# Processor_Interface.net
KiCad netlist of a schematic drawn in Altium Designer
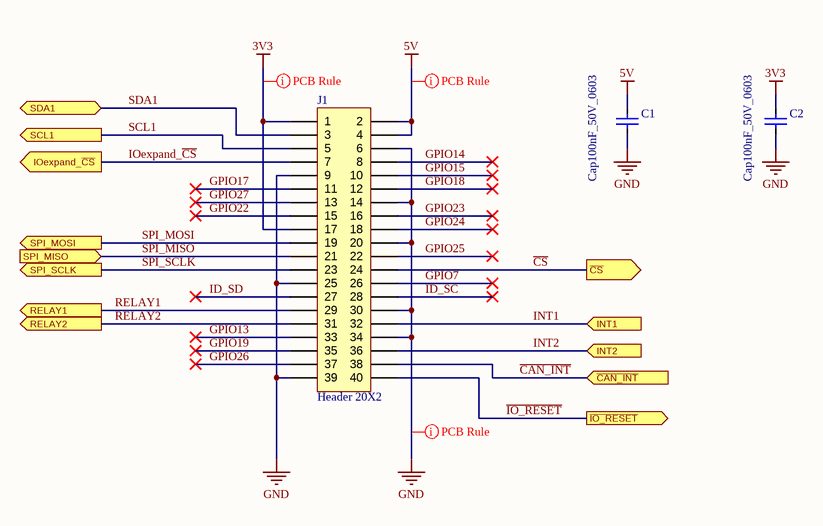
[diagram p0: Processor_Interface.SchDoc]

(export (version "E")
  (design (tool "Eeschema 10.0.6"))
  (components
    (comp (ref "C1")
      (value "Cap100nF_50V_0603")
      (footprint "0603C_L")
      (libsource (lib " Advanced] Training Course - A365") (part "CAP General"))
    )
    (comp (ref "C2")
      (value "Cap100nF_50V_0603")
      (footprint "0603C_L")
      (libsource (lib " Advanced] Training Course - A365") (part "CAP General"))
    )
    (comp (ref "J1")
      (value "Header 20X2")
      (footprint "HDR2X20")
      (description "Header, 20-Pin, Dual row")
      (fields (field (name "PUBLISHER") "Altium Limited"))
      (libsource (lib " Advanced] Training Course - A365") (part "Header 20X2"))
    )
  )
  (nets
    (net (code "1") (name "/CAN_INT") (class "Default")
      (node (ref "J1") (pin "38") (pinfunction "38_38") (pintype "passive"))
    )
    (net (code "2") (name "/GPIO7") (class "Default")
      (node (ref "J1") (pin "26") (pinfunction "26_26") (pintype "passive+no_connect"))
    )
    (net (code "3") (name "/GPIO13") (class "Default")
      (node (ref "J1") (pin "33") (pinfunction "33_33") (pintype "passive+no_connect"))
    )
    (net (code "4") (name "/GPIO14") (class "Default")
      (node (ref "J1") (pin "8") (pinfunction "8_8") (pintype "passive+no_connect"))
    )
    (net (code "5") (name "/GPIO15") (class "Default")
      (node (ref "J1") (pin "10") (pinfunction "10_10") (pintype "passive+no_connect"))
    )
    (net (code "6") (name "/GPIO17") (class "Default")
      (node (ref "J1") (pin "11") (pinfunction "11_11") (pintype "passive+no_connect"))
    )
    (net (code "7") (name "/GPIO18") (class "Default")
      (node (ref "J1") (pin "12") (pinfunction "12_12") (pintype "passive+no_connect"))
    )
    (net (code "8") (name "/GPIO19") (class "Default")
      (node (ref "J1") (pin "35") (pinfunction "35_35") (pintype "passive+no_connect"))
    )
    (net (code "9") (name "/GPIO22") (class "Default")
      (node (ref "J1") (pin "15") (pinfunction "15_15") (pintype "passive+no_connect"))
    )
    (net (code "10") (name "/GPIO23") (class "Default")
      (node (ref "J1") (pin "16") (pinfunction "16_16") (pintype "passive+no_connect"))
    )
    (net (code "11") (name "/GPIO24") (class "Default")
      (node (ref "J1") (pin "18") (pinfunction "18_18") (pintype "passive+no_connect"))
    )
    (net (code "12") (name "/GPIO25") (class "Default")
      (node (ref "J1") (pin "22") (pinfunction "22_22") (pintype "passive+no_connect"))
    )
    (net (code "13") (name "/GPIO26") (class "Default")
      (node (ref "J1") (pin "37") (pinfunction "37_37") (pintype "passive+no_connect"))
    )
    (net (code "14") (name "/GPIO27") (class "Default")
      (node (ref "J1") (pin "13") (pinfunction "13_13") (pintype "passive+no_connect"))
    )
    (net (code "15") (name "/ID_SC") (class "Default")
      (node (ref "J1") (pin "28") (pinfunction "28_28") (pintype "passive+no_connect"))
    )
    (net (code "16") (name "/ID_SD") (class "Default")
      (node (ref "J1") (pin "27") (pinfunction "27_27") (pintype "passive+no_connect"))
    )
    (net (code "17") (name "/INT1") (class "Default")
      (node (ref "J1") (pin "32") (pinfunction "32_32") (pintype "passive"))
    )
    (net (code "18") (name "/INT2") (class "Default")
      (node (ref "J1") (pin "36") (pinfunction "36_36") (pintype "passive"))
    )
    (net (code "19") (name "/IO_RESET") (class "Default")
      (node (ref "J1") (pin "40") (pinfunction "40_40") (pintype "passive"))
    )
    (net (code "20") (name "/IOexpand_~{CS}") (class "Default")
      (node (ref "J1") (pin "7") (pinfunction "7_7") (pintype "passive"))
    )
    (net (code "21") (name "/RELAY1") (class "Default")
      (node (ref "J1") (pin "29") (pinfunction "29_29") (pintype "passive"))
    )
    (net (code "22") (name "/RELAY2") (class "Default")
      (node (ref "J1") (pin "31") (pinfunction "31_31") (pintype "passive"))
    )
    (net (code "23") (name "/SCL1") (class "Default")
      (node (ref "J1") (pin "5") (pinfunction "5_5") (pintype "passive"))
    )
    (net (code "24") (name "/SDA1") (class "Default")
      (node (ref "J1") (pin "3") (pinfunction "3_3") (pintype "passive"))
    )
    (net (code "25") (name "/SPI_MISO") (class "Default")
      (node (ref "J1") (pin "21") (pinfunction "21_21") (pintype "passive"))
    )
    (net (code "26") (name "/SPI_MOSI") (class "Default")
      (node (ref "J1") (pin "19") (pinfunction "19_19") (pintype "passive"))
    )
    (net (code "27") (name "/SPI_SCLK") (class "Default")
      (node (ref "J1") (pin "23") (pinfunction "23_23") (pintype "passive"))
    )
    (net (code "28") (name "/~{CS}") (class "Default")
      (node (ref "J1") (pin "24") (pinfunction "24_24") (pintype "passive"))
    )
    (net (code "29") (name "3V3") (class "Default")
      (node (ref "C2") (pin "2") (pinfunction "2_2") (pintype "passive"))
      (node (ref "J1") (pin "1") (pinfunction "1_1") (pintype "passive"))
      (node (ref "J1") (pin "17") (pinfunction "17_17") (pintype "passive"))
    )
    (net (code "30") (name "5V") (class "Default")
      (node (ref "C1") (pin "2") (pinfunction "2_2") (pintype "passive"))
      (node (ref "J1") (pin "2") (pinfunction "2_2") (pintype "passive"))
      (node (ref "J1") (pin "4") (pinfunction "4_4") (pintype "passive"))
    )
    (net (code "31") (name "GND") (class "Default")
      (node (ref "C1") (pin "1") (pinfunction "1_1") (pintype "passive"))
      (node (ref "C2") (pin "1") (pinfunction "1_1") (pintype "passive"))
      (node (ref "J1") (pin "14") (pinfunction "14_14") (pintype "passive"))
      (node (ref "J1") (pin "20") (pinfunction "20_20") (pintype "passive"))
      (node (ref "J1") (pin "25") (pinfunction "25_25") (pintype "passive"))
      (node (ref "J1") (pin "30") (pinfunction "30_30") (pintype "passive"))
      (node (ref "J1") (pin "34") (pinfunction "34_34") (pintype "passive"))
      (node (ref "J1") (pin "39") (pinfunction "39_39") (pintype "passive"))
      (node (ref "J1") (pin "6") (pinfunction "6_6") (pintype "passive"))
      (node (ref "J1") (pin "9") (pinfunction "9_9") (pintype "passive"))
    )
  )
)
